# MainControll.net
KiCad netlist of a schematic drawn in EAGLE
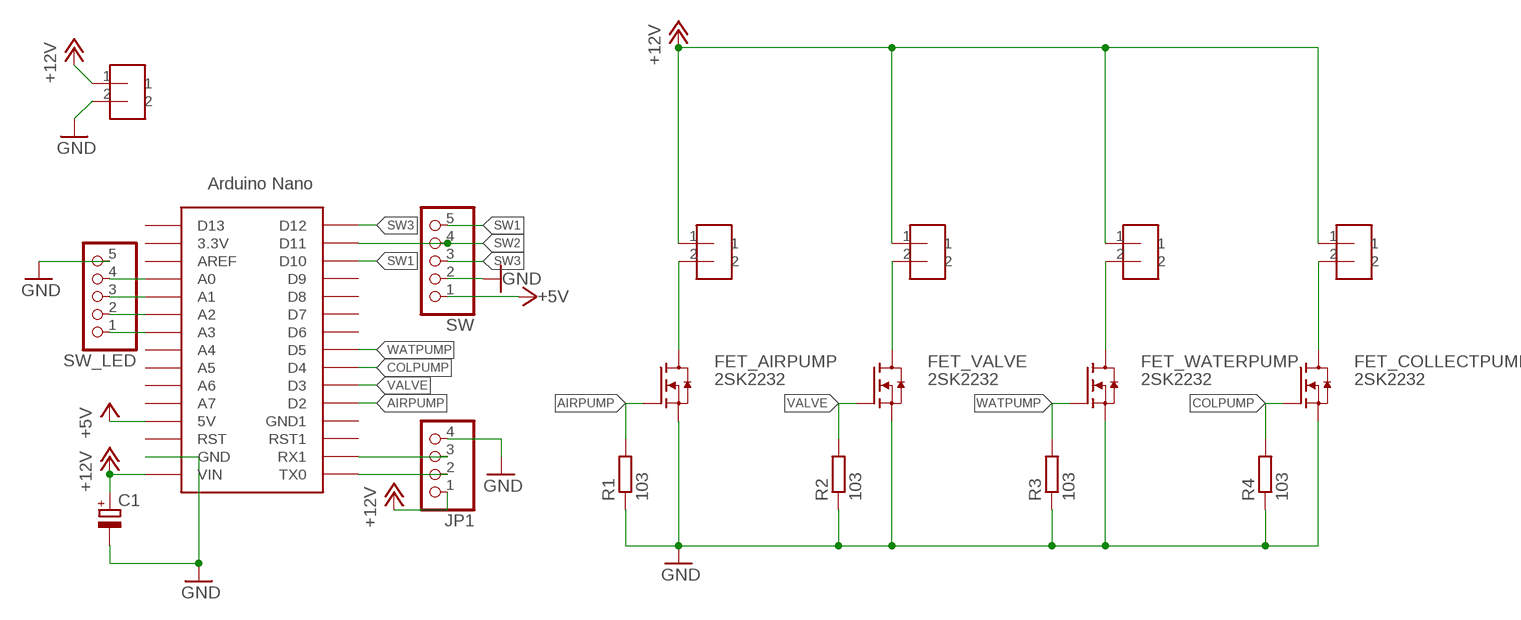
[diagram p0: schematic, sheet 1]

(export (version "E")
  (design (tool "Eeschema 10.0.6"))
  (components
    (comp (ref "C1")
      (value "CPOL-EUE2.5-5")
      (footprint "eagle-import:E2,5-5")
      (libsource (lib "eagle-import") (part "CPOL-EUE2.5-5"))
    )
    (comp (ref "FET_AIRPUMP")
      (value "2SK2232")
      (footprint "eagle-import:TO220")
      (libsource (lib "eagle-import") (part "2SK2232"))
    )
    (comp (ref "FET_COLLECTPUMP")
      (value "2SK2232")
      (footprint "eagle-import:TO220")
      (libsource (lib "eagle-import") (part "2SK2232"))
    )
    (comp (ref "FET_VALVE")
      (value "2SK2232")
      (footprint "eagle-import:TO220")
      (libsource (lib "eagle-import") (part "2SK2232"))
    )
    (comp (ref "FET_WATERPUMP")
      (value "2SK2232")
      (footprint "eagle-import:TO220")
      (libsource (lib "eagle-import") (part "2SK2232"))
    )
    (comp (ref "JP1")
      (value "PINHD-1X4")
      (footprint "eagle-import:1X04")
      (libsource (lib "eagle-import") (part "PINHD-1X4"))
    )
    (comp (ref "R1")
      (value "103")
      (footprint "eagle-import:0204_5")
      (libsource (lib "eagle-import") (part "R-EU_0204/5"))
    )
    (comp (ref "R2")
      (value "103")
      (footprint "eagle-import:0204_5")
      (libsource (lib "eagle-import") (part "R-EU_0204/5"))
    )
    (comp (ref "R3")
      (value "103")
      (footprint "eagle-import:0204_5")
      (libsource (lib "eagle-import") (part "R-EU_0204/5"))
    )
    (comp (ref "R4")
      (value "103")
      (footprint "eagle-import:0204_5")
      (libsource (lib "eagle-import") (part "R-EU_0204/5"))
    )
    (comp (ref "SW")
      (value "PINHD-1X5")
      (footprint "eagle-import:1X05")
      (libsource (lib "eagle-import") (part "PINHD-1X5"))
    )
    (comp (ref "SW_LED")
      (value "PINHD-1X5")
      (footprint "eagle-import:1X05")
      (libsource (lib "eagle-import") (part "PINHD-1X5"))
    )
    (comp (ref "TERMINAL_AIRPUMP")
      (value "TERMINAL_BLOCK_5.08MM")
      (footprint "eagle-import:TERMINAL_BLOCK_5.8MM")
      (libsource (lib "eagle-import") (part "TERMINAL_BLOCK_5.08MM"))
    )
    (comp (ref "TERMINAL_COLLECTPUMP")
      (value "TERMINAL_BLOCK_5.08MM")
      (footprint "eagle-import:TERMINAL_BLOCK_5.8MM")
      (libsource (lib "eagle-import") (part "TERMINAL_BLOCK_5.08MM"))
    )
    (comp (ref "TERMINAL_VALVE")
      (value "TERMINAL_BLOCK_5.08MM")
      (footprint "eagle-import:TERMINAL_BLOCK_5.8MM")
      (libsource (lib "eagle-import") (part "TERMINAL_BLOCK_5.08MM"))
    )
    (comp (ref "TERMINAL_WATERPUMP")
      (value "TERMINAL_BLOCK_5.08MM")
      (footprint "eagle-import:TERMINAL_BLOCK_5.8MM")
      (libsource (lib "eagle-import") (part "TERMINAL_BLOCK_5.08MM"))
    )
    (comp (ref "U$1")
      (value "TERMINAL_BLOCK_5.08MM")
      (footprint "eagle-import:TERMINAL_BLOCK_5.8MM")
      (libsource (lib "eagle-import") (part "TERMINAL_BLOCK_5.08MM"))
    )
    (comp (ref "U$2")
      (value "NANO_DIL_RECEPTOR")
      (footprint "eagle-import:NANO_DIL")
      (libsource (lib "eagle-import") (part "NANO_DIL_RECEPTOR"))
    )
  )
  (nets
    (net (code "1") (name "+5V") (class "Default")
      (node (ref "SW") (pin "1") (pinfunction "1_1") (pintype "passive"))
      (node (ref "U$2") (pin "5V") (pinfunction "5V_5V") (pintype "bidirectional"))
    )
    (net (code "2") (name "+12V") (class "Default")
      (node (ref "C1") (pin "+") (pinfunction "+_+") (pintype "passive"))
      (node (ref "JP1") (pin "1") (pinfunction "1_1") (pintype "passive"))
      (node (ref "TERMINAL_AIRPUMP") (pin "1") (pinfunction "1_1") (pintype "bidirectional"))
      (node (ref "TERMINAL_COLLECTPUMP") (pin "1") (pinfunction "1_1") (pintype "bidirectional"))
      (node (ref "TERMINAL_VALVE") (pin "1") (pinfunction "1_1") (pintype "bidirectional"))
      (node (ref "TERMINAL_WATERPUMP") (pin "1") (pinfunction "1_1") (pintype "bidirectional"))
      (node (ref "U$1") (pin "1") (pinfunction "1_1") (pintype "bidirectional"))
      (node (ref "U$2") (pin "VIN") (pinfunction "VIN_VIN") (pintype "bidirectional"))
    )
    (net (code "3") (name "AIRPUMP") (class "Default")
      (node (ref "FET_AIRPUMP") (pin "1") (pinfunction "G_1") (pintype "passive"))
      (node (ref "R1") (pin "2") (pinfunction "2_2") (pintype "passive"))
      (node (ref "U$2") (pin "D2") (pinfunction "D2_D2") (pintype "bidirectional"))
    )
    (net (code "4") (name "COLPUMP") (class "Default")
      (node (ref "FET_COLLECTPUMP") (pin "1") (pinfunction "G_1") (pintype "passive"))
      (node (ref "R4") (pin "2") (pinfunction "2_2") (pintype "passive"))
      (node (ref "U$2") (pin "D4") (pinfunction "D4_D4") (pintype "bidirectional"))
    )
    (net (code "5") (name "GND") (class "Default")
      (node (ref "C1") (pin "-") (pinfunction "-_-") (pintype "passive"))
      (node (ref "FET_AIRPUMP") (pin "3") (pinfunction "S_3") (pintype "passive"))
      (node (ref "FET_COLLECTPUMP") (pin "3") (pinfunction "S_3") (pintype "passive"))
      (node (ref "FET_VALVE") (pin "3") (pinfunction "S_3") (pintype "passive"))
      (node (ref "FET_WATERPUMP") (pin "3") (pinfunction "S_3") (pintype "passive"))
      (node (ref "JP1") (pin "4") (pinfunction "4_4") (pintype "passive"))
      (node (ref "R1") (pin "1") (pinfunction "1_1") (pintype "passive"))
      (node (ref "R2") (pin "1") (pinfunction "1_1") (pintype "passive"))
      (node (ref "R3") (pin "1") (pinfunction "1_1") (pintype "passive"))
      (node (ref "R4") (pin "1") (pinfunction "1_1") (pintype "passive"))
      (node (ref "SW") (pin "2") (pinfunction "2_2") (pintype "passive"))
      (node (ref "SW_LED") (pin "5") (pinfunction "5_5") (pintype "passive"))
      (node (ref "U$1") (pin "2") (pinfunction "2_2") (pintype "bidirectional"))
      (node (ref "U$2") (pin "GND") (pinfunction "GND_GND") (pintype "bidirectional"))
    )
    (net (code "6") (name "Net-(FET_AIRPUMP-D)") (class "Default")
      (node (ref "FET_AIRPUMP") (pin "2") (pinfunction "D_2") (pintype "passive"))
      (node (ref "TERMINAL_AIRPUMP") (pin "2") (pinfunction "2_2") (pintype "bidirectional"))
    )
    (net (code "7") (name "Net-(FET_COLLECTPUMP-D)") (class "Default")
      (node (ref "FET_COLLECTPUMP") (pin "2") (pinfunction "D_2") (pintype "passive"))
      (node (ref "TERMINAL_COLLECTPUMP") (pin "2") (pinfunction "2_2") (pintype "bidirectional"))
    )
    (net (code "8") (name "Net-(FET_VALVE-D)") (class "Default")
      (node (ref "FET_VALVE") (pin "2") (pinfunction "D_2") (pintype "passive"))
      (node (ref "TERMINAL_VALVE") (pin "2") (pinfunction "2_2") (pintype "bidirectional"))
    )
    (net (code "9") (name "Net-(FET_WATERPUMP-D)") (class "Default")
      (node (ref "FET_WATERPUMP") (pin "2") (pinfunction "D_2") (pintype "passive"))
      (node (ref "TERMINAL_WATERPUMP") (pin "2") (pinfunction "2_2") (pintype "bidirectional"))
    )
    (net (code "10") (name "Net-(JP1-Pad2)") (class "Default")
      (node (ref "JP1") (pin "2") (pinfunction "2_2") (pintype "passive"))
      (node (ref "U$2") (pin "TX0") (pinfunction "TX0_TX0") (pintype "bidirectional"))
    )
    (net (code "11") (name "Net-(JP1-Pad3)") (class "Default")
      (node (ref "JP1") (pin "3") (pinfunction "3_3") (pintype "passive"))
      (node (ref "U$2") (pin "RX1") (pinfunction "RX1_RX1") (pintype "bidirectional"))
    )
    (net (code "12") (name "Net-(SW_LED-Pad1)") (class "Default")
      (node (ref "SW_LED") (pin "1") (pinfunction "1_1") (pintype "passive"))
      (node (ref "U$2") (pin "A3") (pinfunction "A3_A3") (pintype "bidirectional"))
    )
    (net (code "13") (name "Net-(SW_LED-Pad2)") (class "Default")
      (node (ref "SW_LED") (pin "2") (pinfunction "2_2") (pintype "passive"))
      (node (ref "U$2") (pin "A2") (pinfunction "A2_A2") (pintype "bidirectional"))
    )
    (net (code "14") (name "Net-(SW_LED-Pad3)") (class "Default")
      (node (ref "SW_LED") (pin "3") (pinfunction "3_3") (pintype "passive"))
      (node (ref "U$2") (pin "A1") (pinfunction "A1_A1") (pintype "bidirectional"))
    )
    (net (code "15") (name "Net-(SW_LED-Pad4)") (class "Default")
      (node (ref "SW_LED") (pin "4") (pinfunction "4_4") (pintype "passive"))
      (node (ref "U$2") (pin "A0") (pinfunction "A0_A0") (pintype "bidirectional"))
    )
    (net (code "16") (name "SW1") (class "Default")
      (node (ref "SW") (pin "5") (pinfunction "5_5") (pintype "passive"))
      (node (ref "U$2") (pin "D10") (pinfunction "D10_D10") (pintype "bidirectional"))
    )
    (net (code "17") (name "SW2") (class "Default")
      (node (ref "SW") (pin "4") (pinfunction "4_4") (pintype "passive"))
      (node (ref "U$2") (pin "D11") (pinfunction "D11_D11") (pintype "bidirectional"))
    )
    (net (code "18") (name "SW3") (class "Default")
      (node (ref "SW") (pin "3") (pinfunction "3_3") (pintype "passive"))
      (node (ref "U$2") (pin "D12") (pinfunction "D12_D12") (pintype "bidirectional"))
    )
    (net (code "19") (name "VALVE") (class "Default")
      (node (ref "FET_VALVE") (pin "1") (pinfunction "G_1") (pintype "passive"))
      (node (ref "R2") (pin "2") (pinfunction "2_2") (pintype "passive"))
      (node (ref "U$2") (pin "D3") (pinfunction "D3_D3") (pintype "bidirectional"))
    )
    (net (code "20") (name "WATPUMP") (class "Default")
      (node (ref "FET_WATERPUMP") (pin "1") (pinfunction "G_1") (pintype "passive"))
      (node (ref "R3") (pin "2") (pinfunction "2_2") (pintype "passive"))
      (node (ref "U$2") (pin "D5") (pinfunction "D5_D5") (pintype "bidirectional"))
    )
    (net (code "21") (name "unconnected-(U$2-Pad3.3V)") (class "Default")
      (node (ref "U$2") (pin "3.3V") (pinfunction "3.3V_3.3V") (pintype "bidirectional"))
    )
    (net (code "22") (name "unconnected-(U$2-PadA4)") (class "Default")
      (node (ref "U$2") (pin "A4") (pinfunction "A4_A4") (pintype "bidirectional"))
    )
    (net (code "23") (name "unconnected-(U$2-PadA5)") (class "Default")
      (node (ref "U$2") (pin "A5") (pinfunction "A5_A5") (pintype "bidirectional"))
    )
    (net (code "24") (name "unconnected-(U$2-PadA6)") (class "Default")
      (node (ref "U$2") (pin "A6") (pinfunction "A6_A6") (pintype "bidirectional"))
    )
    (net (code "25") (name "unconnected-(U$2-PadA7)") (class "Default")
      (node (ref "U$2") (pin "A7") (pinfunction "A7_A7") (pintype "bidirectional"))
    )
    (net (code "26") (name "unconnected-(U$2-PadAREF)") (class "Default")
      (node (ref "U$2") (pin "AREF") (pinfunction "AREF_AREF") (pintype "bidirectional"))
    )
    (net (code "27") (name "unconnected-(U$2-PadD6)") (class "Default")
      (node (ref "U$2") (pin "D6") (pinfunction "D6_D6") (pintype "bidirectional"))
    )
    (net (code "28") (name "unconnected-(U$2-PadD7)") (class "Default")
      (node (ref "U$2") (pin "D7") (pinfunction "D7_D7") (pintype "bidirectional"))
    )
    (net (code "29") (name "unconnected-(U$2-PadD8)") (class "Default")
      (node (ref "U$2") (pin "D8") (pinfunction "D8_D8") (pintype "bidirectional"))
    )
    (net (code "30") (name "unconnected-(U$2-PadD9)") (class "Default")
      (node (ref "U$2") (pin "D9") (pinfunction "D9_D9") (pintype "bidirectional"))
    )
    (net (code "31") (name "unconnected-(U$2-PadD13)") (class "Default")
      (node (ref "U$2") (pin "D13") (pinfunction "D13_D13") (pintype "bidirectional"))
    )
    (net (code "32") (name "unconnected-(U$2-PadGND1)") (class "Default")
      (node (ref "U$2") (pin "GND1") (pinfunction "GND1_GND1") (pintype "bidirectional"))
    )
    (net (code "33") (name "unconnected-(U$2-PadRST)") (class "Default")
      (node (ref "U$2") (pin "RST") (pinfunction "RST_RST") (pintype "bidirectional"))
    )
    (net (code "34") (name "unconnected-(U$2-PadRST1)") (class "Default")
      (node (ref "U$2") (pin "RST1") (pinfunction "RST1_RST1") (pintype "bidirectional"))
    )
  )
)
